# copter.net
KiCad netlist of a schematic drawn in EAGLE
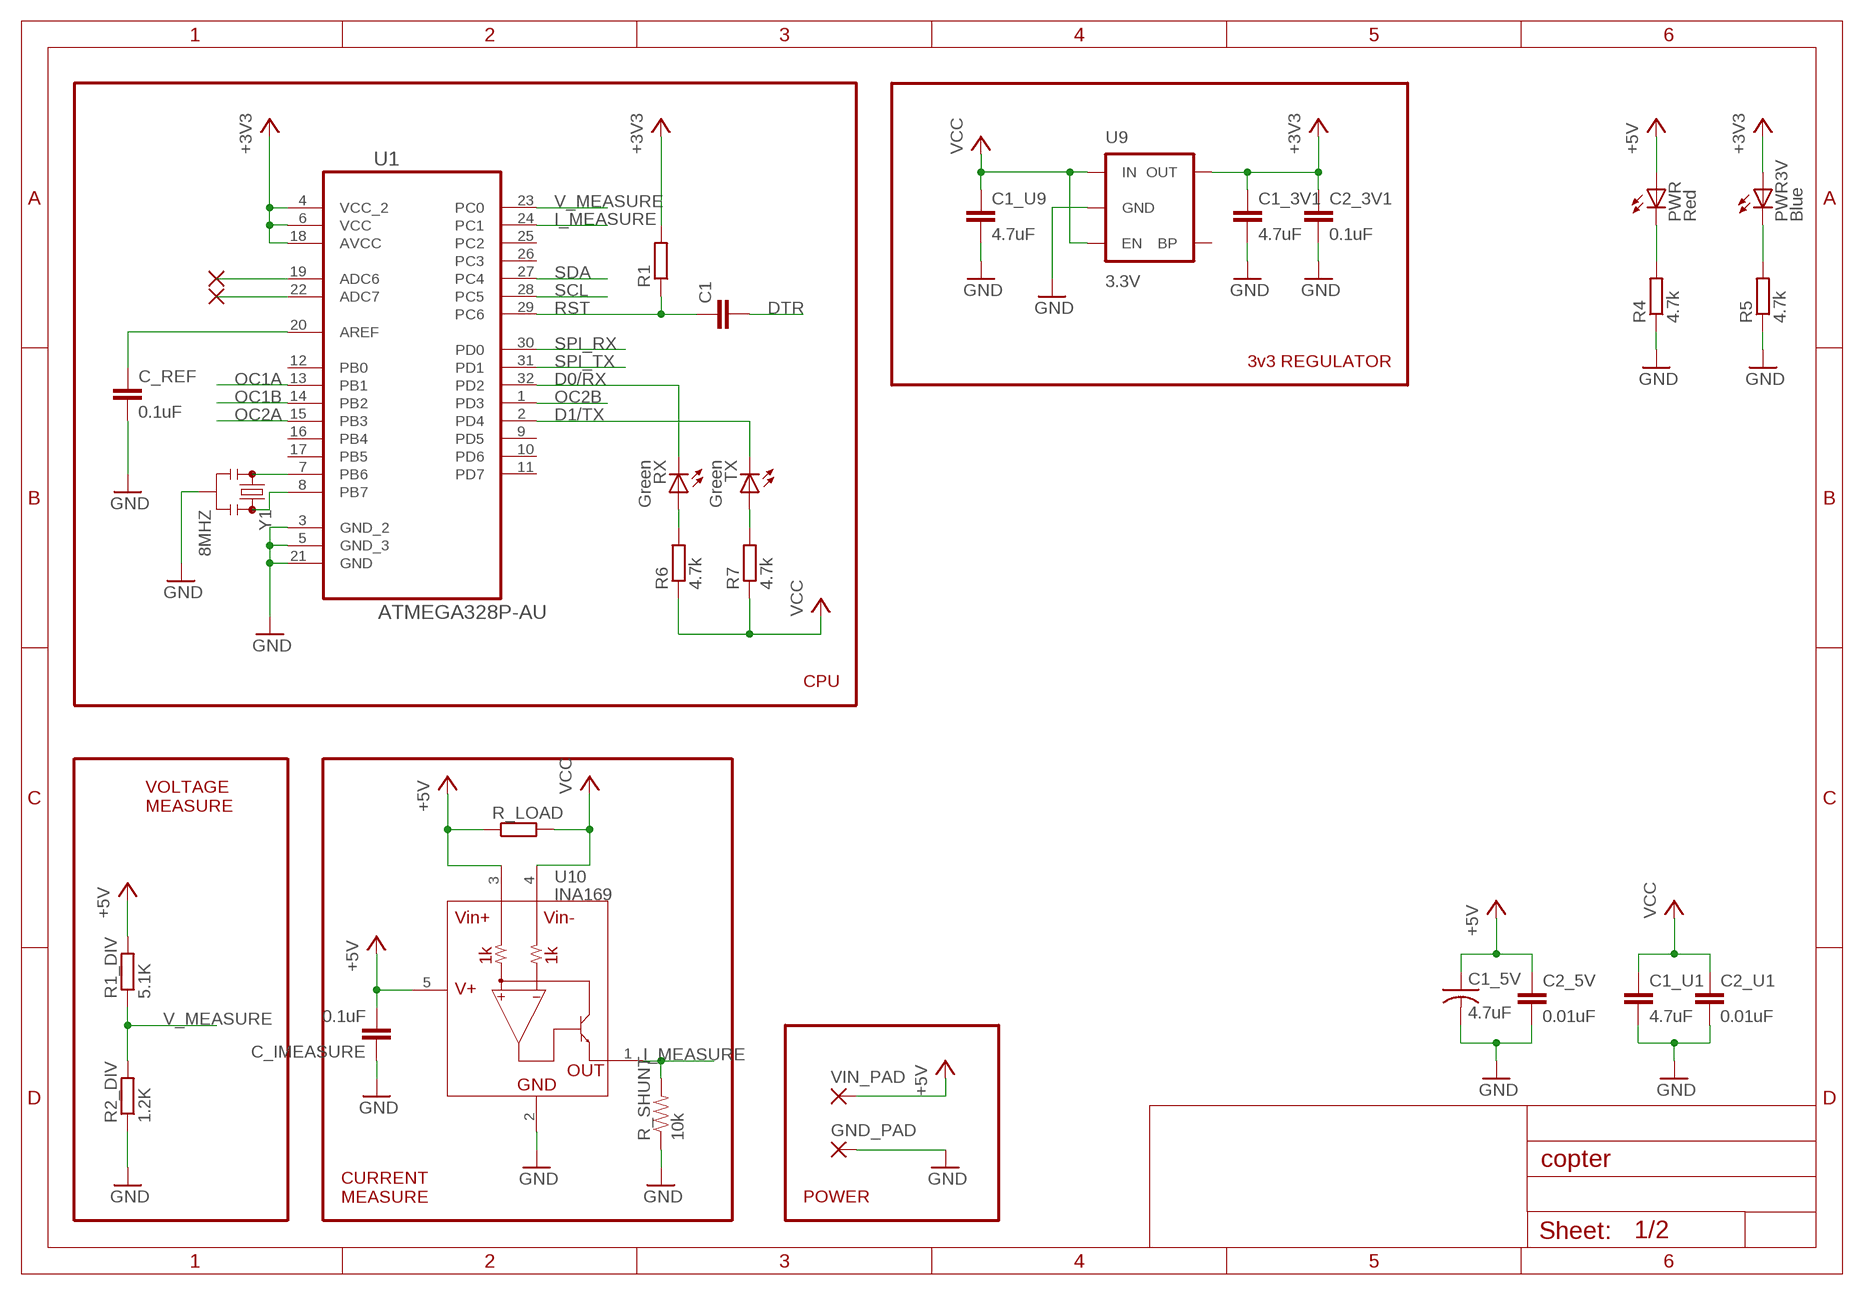
[diagram p0: schematic, sheet 1]
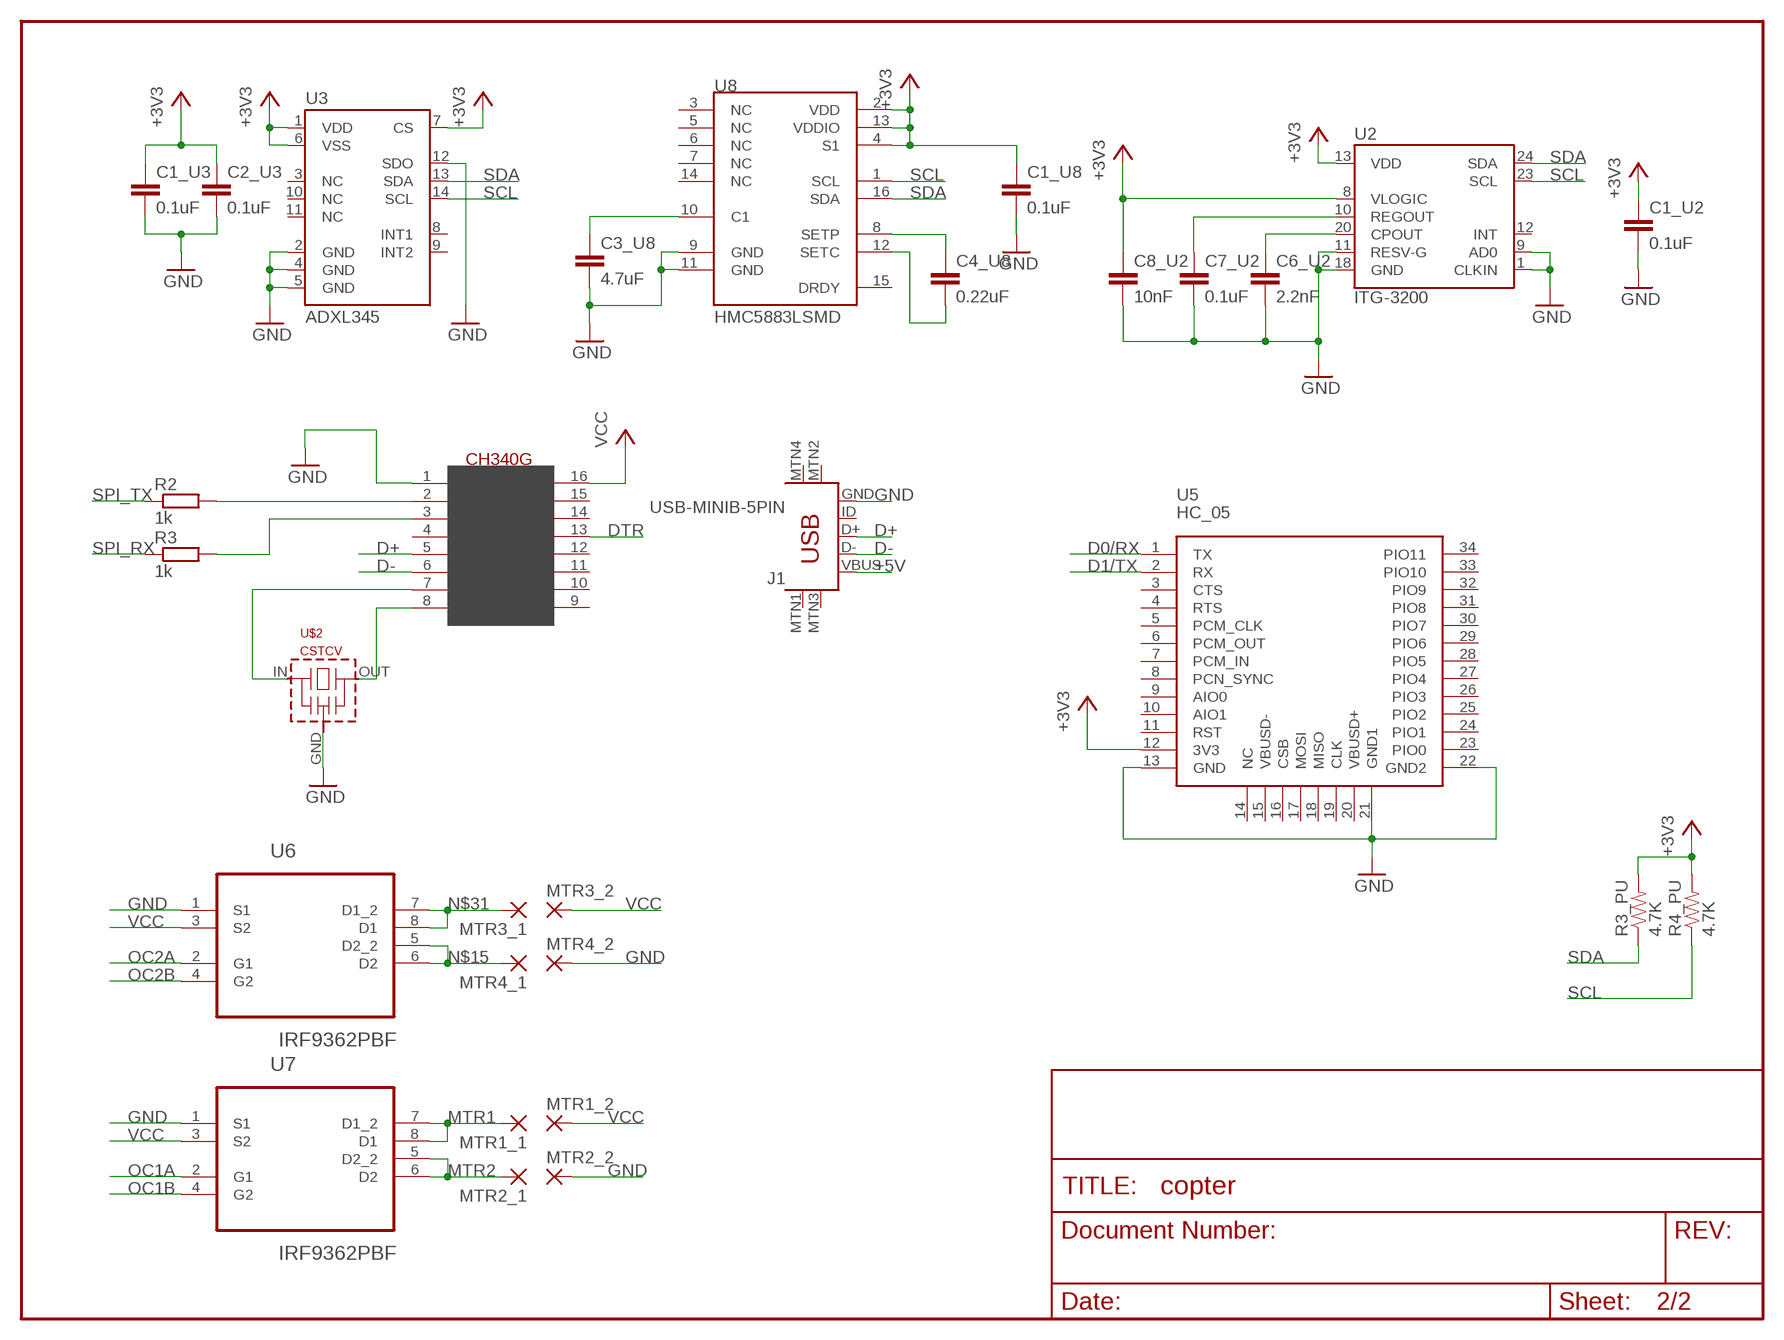
[diagram p1: schematic, sheet 2]

(export (version "E")
  (design (tool "Eeschema 10.0.6"))
  (components
    (comp (ref "C1_U2")
      (value "0.1uF")
      (footprint "eagle-import:0402-CAP")
      (libsource (lib "eagle-import") (part "CAP0402-CAP"))
    )
    (comp (ref "C1_U3")
      (value "0.1uF")
      (footprint "eagle-import:0402-CAP")
      (libsource (lib "eagle-import") (part "CAP0402-CAP"))
    )
    (comp (ref "C1_U8")
      (value "0.1uF")
      (footprint "eagle-import:0402-CAP")
      (libsource (lib "eagle-import") (part "CAP0402-CAP"))
    )
    (comp (ref "C2_U3")
      (value "0.1uF")
      (footprint "eagle-import:0402-CAP")
      (libsource (lib "eagle-import") (part "CAP0402-CAP"))
    )
    (comp (ref "C3_U8")
      (value "4.7uF")
      (footprint "eagle-import:0402-CAP")
      (libsource (lib "eagle-import") (part "CAP0402-CAP"))
    )
    (comp (ref "C4_U8")
      (value "0.22uF")
      (footprint "eagle-import:0402-CAP")
      (libsource (lib "eagle-import") (part "CAP0402-CAP"))
    )
    (comp (ref "C6_U2")
      (value "2.2nF")
      (footprint "eagle-import:0402-CAP")
      (libsource (lib "eagle-import") (part "CAP0402-CAP"))
    )
    (comp (ref "C7_U2")
      (value "0.1uF")
      (footprint "eagle-import:0402-CAP")
      (libsource (lib "eagle-import") (part "CAP0402-CAP"))
    )
    (comp (ref "C8_U2")
      (value "10nF")
      (footprint "eagle-import:0402-CAP")
      (libsource (lib "eagle-import") (part "CAP0402-CAP"))
    )
    (comp (ref "J1")
      (value "USB-MINIB-5PIN")
      (footprint "eagle-import:USB-MINIB")
      (libsource (lib "eagle-import") (part "USB-MINIB-5PIN"))
    )
    (comp (ref "MTR1_1")
      (value "1,6/0,8")
      (footprint "eagle-import:1,6_0,8")
      (libsource (lib "eagle-import") (part "1,6/0,8"))
    )
    (comp (ref "MTR1_2")
      (value "1,6/0,8")
      (footprint "eagle-import:1,6_0,8")
      (libsource (lib "eagle-import") (part "1,6/0,8"))
    )
    (comp (ref "MTR2_1")
      (value "1,6/0,8")
      (footprint "eagle-import:1,6_0,8")
      (libsource (lib "eagle-import") (part "1,6/0,8"))
    )
    (comp (ref "MTR2_2")
      (value "1,6/0,8")
      (footprint "eagle-import:1,6_0,8")
      (libsource (lib "eagle-import") (part "1,6/0,8"))
    )
    (comp (ref "MTR3_1")
      (value "1,6/0,8")
      (footprint "eagle-import:1,6_0,8")
      (libsource (lib "eagle-import") (part "1,6/0,8"))
    )
    (comp (ref "MTR3_2")
      (value "1,6/0,8")
      (footprint "eagle-import:1,6_0,8")
      (libsource (lib "eagle-import") (part "1,6/0,8"))
    )
    (comp (ref "MTR4_1")
      (value "1,6/0,8")
      (footprint "eagle-import:1,6_0,8")
      (libsource (lib "eagle-import") (part "1,6/0,8"))
    )
    (comp (ref "MTR4_2")
      (value "1,6/0,8")
      (footprint "eagle-import:1,6_0,8")
      (libsource (lib "eagle-import") (part "1,6/0,8"))
    )
    (comp (ref "R2")
      (value "1k")
      (footprint "eagle-import:R0402")
      (libsource (lib "eagle-import") (part "resistor_R-EU_R0402"))
    )
    (comp (ref "R3")
      (value "1k")
      (footprint "eagle-import:R0402")
      (libsource (lib "eagle-import") (part "resistor_R-EU_R0402"))
    )
    (comp (ref "R3_PU")
      (value "4.7K")
      (footprint "eagle-import:0402-RES")
      (libsource (lib "eagle-import") (part "RESISTOR0402-RES"))
    )
    (comp (ref "R4_PU")
      (value "4.7K")
      (footprint "eagle-import:0402-RES")
      (libsource (lib "eagle-import") (part "RESISTOR0402-RES"))
    )
    (comp (ref "U$1")
      (value "CH340G")
      (footprint "eagle-import:SOIC16")
      (libsource (lib "eagle-import") (part "CH340G"))
    )
    (comp (ref "U$2")
      (value "CSTCV")
      (footprint "eagle-import:CSTCV")
      (libsource (lib "eagle-import") (part "CSTCV"))
    )
    (comp (ref "U2")
      (value "ITG-3200")
      (footprint "eagle-import:QFN-24")
      (libsource (lib "eagle-import") (part "ITG-3200"))
    )
    (comp (ref "U3")
      (value "ADXL345")
      (footprint "eagle-import:LGA14")
      (libsource (lib "eagle-import") (part "ADXL345"))
    )
    (comp (ref "U5")
      (value "HC_05")
      (footprint "eagle-import:BLUETOOTH_SMD")
      (libsource (lib "eagle-import") (part "HC_05"))
    )
    (comp (ref "U6")
      (value "IRF9362PBF")
      (footprint "eagle-import:SOIC127P600X175-8N")
      (libsource (lib "eagle-import") (part "IRF9362PBF"))
    )
    (comp (ref "U7")
      (value "IRF9362PBF")
      (footprint "eagle-import:SOIC127P600X175-8N")
      (libsource (lib "eagle-import") (part "IRF9362PBF"))
    )
    (comp (ref "U8")
      (value "HMC5883LSMD")
      (footprint "eagle-import:16LPCC")
      (libsource (lib "eagle-import") (part "HMC5883LSMD"))
    )
    (comp (ref "C1")
      (value "C-EUC0402")
      (footprint "eagle-import:C0402")
      (libsource (lib "eagle-import") (part "C-EUC0402"))
    )
    (comp (ref "C1_3V1")
      (value "4.7uF")
      (footprint "eagle-import:0402-CAP")
      (libsource (lib "eagle-import") (part "CAP0402-CAP"))
    )
    (comp (ref "C1_5V")
      (value "4.7uF")
      (footprint "eagle-import:C1210K")
      (libsource (lib "eagle-import") (part "C-USC1210K"))
    )
    (comp (ref "C1_U1")
      (value "4.7uF")
      (footprint "eagle-import:C1206")
      (libsource (lib "eagle-import") (part "resistor_C-EUC1206"))
    )
    (comp (ref "C1_U9")
      (value "4.7uF")
      (footprint "eagle-import:0402-CAP")
      (libsource (lib "eagle-import") (part "CAP0402-CAP"))
    )
    (comp (ref "C2_3V1")
      (value "0.1uF")
      (footprint "eagle-import:0402-CAP")
      (libsource (lib "eagle-import") (part "CAP0402-CAP"))
    )
    (comp (ref "C2_5V")
      (value "0.01uF")
      (footprint "eagle-import:C0402")
      (libsource (lib "eagle-import") (part "resistor_C-EUC0402"))
    )
    (comp (ref "C2_U1")
      (value "0.01uF")
      (footprint "eagle-import:C0402")
      (libsource (lib "eagle-import") (part "resistor_C-EUC0402"))
    )
    (comp (ref "C_IMEASURE")
      (value "0.1uF")
      (footprint "eagle-import:0603-CAP")
      (libsource (lib "eagle-import") (part "SparkFun-Passives_CAP0603-CAP"))
    )
    (comp (ref "C_REF")
      (value "0.1uF")
      (footprint "eagle-import:C0402")
      (libsource (lib "eagle-import") (part "resistor_C-EUC0402"))
    )
    (comp (ref "GND_PAD")
      (value "1,6/0,8")
      (footprint "eagle-import:1,6_0,8")
      (libsource (lib "eagle-import") (part "1,6/0,8"))
    )
    (comp (ref "PWR")
      (value "Red")
      (footprint "eagle-import:LED-0603")
      (libsource (lib "eagle-import") (part "LED0603"))
    )
    (comp (ref "PWR3V")
      (value "Blue")
      (footprint "eagle-import:LED-0603")
      (libsource (lib "eagle-import") (part "LED0603"))
    )
    (comp (ref "R1")
      (value "R-EU_R0402")
      (footprint "eagle-import:R0402")
      (libsource (lib "eagle-import") (part "R-EU_R0402"))
    )
    (comp (ref "R1_DIV")
      (value "5.1K")
      (footprint "eagle-import:R0402")
      (libsource (lib "eagle-import") (part "resistor_R-EU_R0402"))
    )
    (comp (ref "R2_DIV")
      (value "1.2K")
      (footprint "eagle-import:R0402")
      (libsource (lib "eagle-import") (part "resistor_R-EU_R0402"))
    )
    (comp (ref "R4")
      (value "4.7k")
      (footprint "eagle-import:R0402")
      (libsource (lib "eagle-import") (part "R-EU_R0402"))
    )
    (comp (ref "R5")
      (value "4.7k")
      (footprint "eagle-import:R0402")
      (libsource (lib "eagle-import") (part "R-EU_R0402"))
    )
    (comp (ref "R6")
      (value "4.7k")
      (footprint "eagle-import:R0402")
      (libsource (lib "eagle-import") (part "R-EU_R0402"))
    )
    (comp (ref "R7")
      (value "4.7k")
      (footprint "eagle-import:R0402")
      (libsource (lib "eagle-import") (part "R-EU_R0402"))
    )
    (comp (ref "RX")
      (value "Green")
      (footprint "eagle-import:LED-0603")
      (libsource (lib "eagle-import") (part "LED0603"))
    )
    (comp (ref "R_LOAD")
      (value "R-EU_0309/10")
      (footprint "eagle-import:0309_10")
      (fields (field (name "SIZE") "1206") (field (name "TOL") "1%"))
      (libsource (lib "eagle-import") (part "resistor_R-EU_0309/10"))
    )
    (comp (ref "R_SHUNT")
      (value "10k")
      (footprint "eagle-import:0603-RES")
      (fields (field (name "TOL") "1%"))
      (libsource (lib "eagle-import") (part "RESISTOR0603"))
    )
    (comp (ref "TX")
      (value "Green")
      (footprint "eagle-import:LED-0603")
      (libsource (lib "eagle-import") (part "LED0603"))
    )
    (comp (ref "U1")
      (value "ATMEGA328P-AU")
      (footprint "eagle-import:QFP80P900X900X120-32N")
      (libsource (lib "eagle-import") (part "ATMEGA328P-AU"))
    )
    (comp (ref "U9")
      (value "3.3V")
      (footprint "eagle-import:SOT23-5")
      (libsource (lib "eagle-import") (part "V_REG_LDOSMD"))
    )
    (comp (ref "U10")
      (value "INA169")
      (footprint "eagle-import:SOT23-5")
      (libsource (lib "eagle-import") (part "INA169"))
    )
    (comp (ref "VIN_PAD")
      (value "1,6/0,8")
      (footprint "eagle-import:1,6_0,8")
      (libsource (lib "eagle-import") (part "1,6/0,8"))
    )
    (comp (ref "Y1")
      (value "8MHZ")
      (footprint "eagle-import:RESONATOR-SMD")
      (libsource (lib "eagle-import") (part "RESONATOR8MHZ"))
    )
  )
  (nets
    (net (code "1") (name "+3V3") (class "Default")
      (node (ref "C1_3V1") (pin "1") (pinfunction "1_1") (pintype "passive"))
      (node (ref "C1_U2") (pin "1") (pinfunction "1_1") (pintype "passive"))
      (node (ref "C1_U3") (pin "1") (pinfunction "1_1") (pintype "passive"))
      (node (ref "C1_U8") (pin "1") (pinfunction "1_1") (pintype "passive"))
      (node (ref "C2_3V1") (pin "1") (pinfunction "1_1") (pintype "passive"))
      (node (ref "C2_U3") (pin "1") (pinfunction "1_1") (pintype "passive"))
      (node (ref "C8_U2") (pin "1") (pinfunction "1_1") (pintype "passive"))
      (node (ref "PWR3V") (pin "A") (pinfunction "A_A") (pintype "passive"))
      (node (ref "R1") (pin "2") (pinfunction "2_2") (pintype "passive"))
      (node (ref "R3_PU") (pin "2") (pinfunction "2_2") (pintype "passive"))
      (node (ref "R4_PU") (pin "2") (pinfunction "2_2") (pintype "passive"))
      (node (ref "U1") (pin "18") (pinfunction "AVCC_18") (pintype "power_in"))
      (node (ref "U1") (pin "4") (pinfunction "VCC_2_4") (pintype "power_in"))
      (node (ref "U1") (pin "6") (pinfunction "VCC_6") (pintype "power_in"))
      (node (ref "U2") (pin "13") (pinfunction "VDD_13") (pintype "bidirectional"))
      (node (ref "U2") (pin "8") (pinfunction "VLOGIC_8") (pintype "bidirectional"))
      (node (ref "U3") (pin "1") (pinfunction "VDD_1") (pintype "bidirectional"))
      (node (ref "U3") (pin "6") (pinfunction "VSS_6") (pintype "bidirectional"))
      (node (ref "U3") (pin "7") (pinfunction "CS_7") (pintype "bidirectional"))
      (node (ref "U5") (pin "12") (pinfunction "3V3_12") (pintype "bidirectional"))
      (node (ref "U8") (pin "13") (pinfunction "VDDIO_13") (pintype "bidirectional"))
      (node (ref "U8") (pin "2") (pinfunction "VDD_2") (pintype "bidirectional"))
      (node (ref "U8") (pin "4") (pinfunction "S1_4") (pintype "bidirectional"))
      (node (ref "U9") (pin "5") (pinfunction "OUT_5") (pintype "passive"))
    )
    (net (code "2") (name "+5V") (class "Default")
      (node (ref "C1_5V") (pin "1") (pinfunction "1_1") (pintype "passive"))
      (node (ref "C2_5V") (pin "1") (pinfunction "1_1") (pintype "passive"))
      (node (ref "C_IMEASURE") (pin "2") (pinfunction "2_2") (pintype "passive"))
      (node (ref "J1") (pin "VBUS") (pinfunction "VBUS_VBUS") (pintype "bidirectional"))
      (node (ref "PWR") (pin "A") (pinfunction "A_A") (pintype "passive"))
      (node (ref "R1_DIV") (pin "2") (pinfunction "2_2") (pintype "passive"))
      (node (ref "R_LOAD") (pin "1") (pinfunction "1_1") (pintype "passive"))
      (node (ref "U10") (pin "3") (pinfunction "VIN+_3") (pintype "bidirectional"))
      (node (ref "U10") (pin "5") (pinfunction "V+_5") (pintype "bidirectional"))
      (node (ref "VIN_PAD") (pin "1") (pinfunction "P_1") (pintype "passive"))
    )
    (net (code "3") (name "D+") (class "Default")
      (node (ref "J1") (pin "D+") (pinfunction "D+_D+") (pintype "bidirectional"))
      (node (ref "U$1") (pin "5") (pinfunction "D+_5") (pintype "bidirectional"))
    )
    (net (code "4") (name "D-") (class "Default")
      (node (ref "J1") (pin "D-") (pinfunction "D-_D-") (pintype "bidirectional"))
      (node (ref "U$1") (pin "6") (pinfunction "D-_6") (pintype "bidirectional"))
    )
    (net (code "5") (name "D0{slash}RX") (class "Default")
      (node (ref "RX") (pin "C") (pinfunction "C_C") (pintype "passive"))
      (node (ref "U1") (pin "32") (pinfunction "PD2_32") (pintype "bidirectional"))
      (node (ref "U5") (pin "1") (pinfunction "TX_1") (pintype "bidirectional"))
    )
    (net (code "6") (name "D1{slash}TX") (class "Default")
      (node (ref "TX") (pin "C") (pinfunction "C_C") (pintype "passive"))
      (node (ref "U1") (pin "2") (pinfunction "PD4_2") (pintype "bidirectional"))
      (node (ref "U5") (pin "2") (pinfunction "RX_2") (pintype "bidirectional"))
    )
    (net (code "7") (name "DTR") (class "Default")
      (node (ref "C1") (pin "2") (pinfunction "2_2") (pintype "passive"))
      (node (ref "U$1") (pin "13") (pinfunction "DTR_13") (pintype "bidirectional"))
    )
    (net (code "8") (name "GND") (class "Default")
      (node (ref "C1_3V1") (pin "2") (pinfunction "2_2") (pintype "passive"))
      (node (ref "C1_5V") (pin "2") (pinfunction "2_2") (pintype "passive"))
      (node (ref "C1_U1") (pin "2") (pinfunction "2_2") (pintype "passive"))
      (node (ref "C1_U2") (pin "2") (pinfunction "2_2") (pintype "passive"))
      (node (ref "C1_U3") (pin "2") (pinfunction "2_2") (pintype "passive"))
      (node (ref "C1_U8") (pin "2") (pinfunction "2_2") (pintype "passive"))
      (node (ref "C1_U9") (pin "2") (pinfunction "2_2") (pintype "passive"))
      (node (ref "C2_3V1") (pin "2") (pinfunction "2_2") (pintype "passive"))
      (node (ref "C2_5V") (pin "2") (pinfunction "2_2") (pintype "passive"))
      (node (ref "C2_U1") (pin "2") (pinfunction "2_2") (pintype "passive"))
      (node (ref "C2_U3") (pin "2") (pinfunction "2_2") (pintype "passive"))
      (node (ref "C3_U8") (pin "2") (pinfunction "2_2") (pintype "passive"))
      (node (ref "C6_U2") (pin "2") (pinfunction "2_2") (pintype "passive"))
      (node (ref "C7_U2") (pin "2") (pinfunction "2_2") (pintype "passive"))
      (node (ref "C8_U2") (pin "2") (pinfunction "2_2") (pintype "passive"))
      (node (ref "C_IMEASURE") (pin "1") (pinfunction "1_1") (pintype "passive"))
      (node (ref "C_REF") (pin "2") (pinfunction "2_2") (pintype "passive"))
      (node (ref "GND_PAD") (pin "1") (pinfunction "P_1") (pintype "passive"))
      (node (ref "J1") (pin "GND") (pinfunction "GND_GND") (pintype "bidirectional"))
      (node (ref "MTR2_2") (pin "1") (pinfunction "P_1") (pintype "passive"))
      (node (ref "MTR4_2") (pin "1") (pinfunction "P_1") (pintype "passive"))
      (node (ref "R2_DIV") (pin "1") (pinfunction "1_1") (pintype "passive"))
      (node (ref "R4") (pin "1") (pinfunction "1_1") (pintype "passive"))
      (node (ref "R5") (pin "1") (pinfunction "1_1") (pintype "passive"))
      (node (ref "R_SHUNT") (pin "1") (pinfunction "1_1") (pintype "passive"))
      (node (ref "U$1") (pin "1") (pinfunction "GND_1") (pintype "bidirectional"))
      (node (ref "U$2") (pin "GND") (pinfunction "GND_GND") (pintype "power_in"))
      (node (ref "U1") (pin "21") (pinfunction "GND_21") (pintype "passive"))
      (node (ref "U1") (pin "3") (pinfunction "GND_2_3") (pintype "passive"))
      (node (ref "U1") (pin "5") (pinfunction "GND_3_5") (pintype "passive"))
      (node (ref "U10") (pin "2") (pinfunction "GND_2") (pintype "bidirectional"))
      (node (ref "U2") (pin "1") (pinfunction "CLKIN_1") (pintype "bidirectional"))
      (node (ref "U2") (pin "11") (pinfunction "RESV-G_11") (pintype "bidirectional"))
      (node (ref "U2") (pin "18") (pinfunction "GND_18") (pintype "bidirectional"))
      (node (ref "U2") (pin "9") (pinfunction "AD0_9") (pintype "bidirectional"))
      (node (ref "U3") (pin "12") (pinfunction "SDO_12") (pintype "bidirectional"))
      (node (ref "U3") (pin "2") (pinfunction "GND_2") (pintype "bidirectional"))
      (node (ref "U3") (pin "4") (pinfunction "GND_4") (pintype "bidirectional"))
      (node (ref "U3") (pin "5") (pinfunction "GND_5") (pintype "bidirectional"))
      (node (ref "U5") (pin "13") (pinfunction "GND_13") (pintype "bidirectional"))
      (node (ref "U5") (pin "21") (pinfunction "GND1_21") (pintype "bidirectional"))
      (node (ref "U5") (pin "22") (pinfunction "GND2_22") (pintype "bidirectional"))
      (node (ref "U6") (pin "1") (pinfunction "S1_1") (pintype "passive"))
      (node (ref "U7") (pin "1") (pinfunction "S1_1") (pintype "passive"))
      (node (ref "U8") (pin "11") (pinfunction "GND_11") (pintype "bidirectional"))
      (node (ref "U8") (pin "9") (pinfunction "GND_9") (pintype "bidirectional"))
      (node (ref "U9") (pin "2") (pinfunction "GND_2") (pintype "input"))
      (node (ref "Y1") (pin "2") (pinfunction "2_2") (pintype "passive"))
    )
    (net (code "9") (name "I_MEASURE") (class "Default")
      (node (ref "R_SHUNT") (pin "2") (pinfunction "2_2") (pintype "passive"))
      (node (ref "U1") (pin "24") (pinfunction "PC1_24") (pintype "bidirectional"))
      (node (ref "U10") (pin "1") (pinfunction "OUT_1") (pintype "bidirectional"))
    )
    (net (code "10") (name "MTR1") (class "Default")
      (node (ref "MTR1_1") (pin "1") (pinfunction "P_1") (pintype "passive"))
      (node (ref "U7") (pin "7") (pinfunction "D1_2_7") (pintype "passive"))
      (node (ref "U7") (pin "8") (pinfunction "D1_8") (pintype "passive"))
    )
    (net (code "11") (name "MTR2") (class "Default")
      (node (ref "MTR2_1") (pin "1") (pinfunction "P_1") (pintype "passive"))
      (node (ref "U7") (pin "5") (pinfunction "D2_2_5") (pintype "passive"))
      (node (ref "U7") (pin "6") (pinfunction "D2_6") (pintype "passive"))
    )
    (net (code "12") (name "N$15") (class "Default")
      (node (ref "MTR4_1") (pin "1") (pinfunction "P_1") (pintype "passive"))
      (node (ref "U6") (pin "5") (pinfunction "D2_2_5") (pintype "passive"))
      (node (ref "U6") (pin "6") (pinfunction "D2_6") (pintype "passive"))
    )
    (net (code "13") (name "N$31") (class "Default")
      (node (ref "MTR3_1") (pin "1") (pinfunction "P_1") (pintype "passive"))
      (node (ref "U6") (pin "7") (pinfunction "D1_2_7") (pintype "passive"))
      (node (ref "U6") (pin "8") (pinfunction "D1_8") (pintype "passive"))
    )
    (net (code "14") (name "Net-(PWR-PadC)") (class "Default")
      (node (ref "PWR") (pin "C") (pinfunction "C_C") (pintype "passive"))
      (node (ref "R4") (pin "2") (pinfunction "2_2") (pintype "passive"))
    )
    (net (code "15") (name "Net-(PWR3V-PadC)") (class "Default")
      (node (ref "PWR3V") (pin "C") (pinfunction "C_C") (pintype "passive"))
      (node (ref "R5") (pin "2") (pinfunction "2_2") (pintype "passive"))
    )
    (net (code "16") (name "Net-(R6-Pad2)") (class "Default")
      (node (ref "R6") (pin "2") (pinfunction "2_2") (pintype "passive"))
      (node (ref "RX") (pin "A") (pinfunction "A_A") (pintype "passive"))
    )
    (net (code "17") (name "Net-(R7-Pad2)") (class "Default")
      (node (ref "R7") (pin "2") (pinfunction "2_2") (pintype "passive"))
      (node (ref "TX") (pin "A") (pinfunction "A_A") (pintype "passive"))
    )
    (net (code "18") (name "Net-(U$1-RX)") (class "Default")
      (node (ref "R3") (pin "2") (pinfunction "2_2") (pintype "passive"))
      (node (ref "U$1") (pin "3") (pinfunction "RX_3") (pintype "bidirectional"))
    )
    (net (code "19") (name "Net-(U$1-TX)") (class "Default")
      (node (ref "R2") (pin "2") (pinfunction "2_2") (pintype "passive"))
      (node (ref "U$1") (pin "2") (pinfunction "TX_2") (pintype "bidirectional"))
    )
    (net (code "20") (name "Net-(U$1-XI)") (class "Default")
      (node (ref "U$1") (pin "7") (pinfunction "XI_7") (pintype "bidirectional"))
      (node (ref "U$2") (pin "IN") (pinfunction "IN_IN") (pintype "input"))
    )
    (net (code "21") (name "Net-(U$1-XO)") (class "Default")
      (node (ref "U$1") (pin "8") (pinfunction "XO_8") (pintype "bidirectional"))
      (node (ref "U$2") (pin "OUT") (pinfunction "OUT_OUT") (pintype "output"))
    )
    (net (code "22") (name "Net-(U1-AREF)") (class "Default")
      (node (ref "C_REF") (pin "1") (pinfunction "1_1") (pintype "passive"))
      (node (ref "U1") (pin "20") (pinfunction "AREF_20") (pintype "input"))
    )
    (net (code "23") (name "Net-(U1-PB6)") (class "Default")
      (node (ref "U1") (pin "7") (pinfunction "PB6_7") (pintype "bidirectional"))
      (node (ref "Y1") (pin "1") (pinfunction "1_1") (pintype "passive"))
    )
    (net (code "24") (name "Net-(U1-PB7)") (class "Default")
      (node (ref "U1") (pin "8") (pinfunction "PB7_8") (pintype "bidirectional"))
      (node (ref "Y1") (pin "3") (pinfunction "3_3") (pintype "passive"))
    )
    (net (code "25") (name "Net-(U2-CPOUT)") (class "Default")
      (node (ref "C6_U2") (pin "1") (pinfunction "1_1") (pintype "passive"))
      (node (ref "U2") (pin "20") (pinfunction "CPOUT_20") (pintype "bidirectional"))
    )
    (net (code "26") (name "Net-(U2-REGOUT)") (class "Default")
      (node (ref "C7_U2") (pin "1") (pinfunction "1_1") (pintype "passive"))
      (node (ref "U2") (pin "10") (pinfunction "REGOUT_10") (pintype "bidirectional"))
    )
    (net (code "27") (name "Net-(U8-C1)") (class "Default")
      (node (ref "C3_U8") (pin "1") (pinfunction "1_1") (pintype "passive"))
      (node (ref "U8") (pin "10") (pinfunction "C1_10") (pintype "bidirectional"))
    )
    (net (code "28") (name "Net-(U8-SETC)") (class "Default")
      (node (ref "C4_U8") (pin "2") (pinfunction "2_2") (pintype "passive"))
      (node (ref "U8") (pin "12") (pinfunction "SETC_12") (pintype "bidirectional"))
    )
    (net (code "29") (name "Net-(U8-SETP)") (class "Default")
      (node (ref "C4_U8") (pin "1") (pinfunction "1_1") (pintype "passive"))
      (node (ref "U8") (pin "8") (pinfunction "SETP_8") (pintype "bidirectional"))
    )
    (net (code "30") (name "OC1A") (class "Default")
      (node (ref "U1") (pin "13") (pinfunction "PB1_13") (pintype "bidirectional"))
      (node (ref "U7") (pin "2") (pinfunction "G1_2") (pintype "passive"))
    )
    (net (code "31") (name "OC1B") (class "Default")
      (node (ref "U1") (pin "14") (pinfunction "PB2_14") (pintype "bidirectional"))
      (node (ref "U7") (pin "4") (pinfunction "G2_4") (pintype "passive"))
    )
    (net (code "32") (name "OC2A") (class "Default")
      (node (ref "U1") (pin "15") (pinfunction "PB3_15") (pintype "bidirectional"))
      (node (ref "U6") (pin "2") (pinfunction "G1_2") (pintype "passive"))
    )
    (net (code "33") (name "OC2B") (class "Default")
      (node (ref "U1") (pin "1") (pinfunction "PD3_1") (pintype "bidirectional"))
      (node (ref "U6") (pin "4") (pinfunction "G2_4") (pintype "passive"))
    )
    (net (code "34") (name "RST") (class "Default")
      (node (ref "C1") (pin "1") (pinfunction "1_1") (pintype "passive"))
      (node (ref "R1") (pin "1") (pinfunction "1_1") (pintype "passive"))
      (node (ref "U1") (pin "29") (pinfunction "PC6_29") (pintype "bidirectional"))
    )
    (net (code "35") (name "SCL") (class "Default")
      (node (ref "R4_PU") (pin "1") (pinfunction "1_1") (pintype "passive"))
      (node (ref "U1") (pin "28") (pinfunction "PC5_28") (pintype "bidirectional"))
      (node (ref "U2") (pin "23") (pinfunction "SCL_23") (pintype "bidirectional"))
      (node (ref "U3") (pin "14") (pinfunction "SCL_14") (pintype "bidirectional"))
      (node (ref "U8") (pin "1") (pinfunction "SCL_1") (pintype "bidirectional"))
    )
    (net (code "36") (name "SDA") (class "Default")
      (node (ref "R3_PU") (pin "1") (pinfunction "1_1") (pintype "passive"))
      (node (ref "U1") (pin "27") (pinfunction "PC4_27") (pintype "bidirectional"))
      (node (ref "U2") (pin "24") (pinfunction "SDA_24") (pintype "bidirectional"))
      (node (ref "U3") (pin "13") (pinfunction "SDA_13") (pintype "bidirectional"))
      (node (ref "U8") (pin "16") (pinfunction "SDA_16") (pintype "bidirectional"))
    )
    (net (code "37") (name "SPI_RX") (class "Default")
      (node (ref "R3") (pin "1") (pinfunction "1_1") (pintype "passive"))
      (node (ref "U1") (pin "30") (pinfunction "PD0_30") (pintype "bidirectional"))
    )
    (net (code "38") (name "SPI_TX") (class "Default")
      (node (ref "R2") (pin "1") (pinfunction "1_1") (pintype "passive"))
      (node (ref "U1") (pin "31") (pinfunction "PD1_31") (pintype "bidirectional"))
    )
    (net (code "39") (name "VCC") (class "Default")
      (node (ref "C1_U1") (pin "1") (pinfunction "1_1") (pintype "passive"))
      (node (ref "C1_U9") (pin "1") (pinfunction "1_1") (pintype "passive"))
      (node (ref "C2_U1") (pin "1") (pinfunction "1_1") (pintype "passive"))
      (node (ref "MTR1_2") (pin "1") (pinfunction "P_1") (pintype "passive"))
      (node (ref "MTR3_2") (pin "1") (pinfunction "P_1") (pintype "passive"))
      (node (ref "R6") (pin "1") (pinfunction "1_1") (pintype "passive"))
      (node (ref "R7") (pin "1") (pinfunction "1_1") (pintype "passive"))
      (node (ref "R_LOAD") (pin "2") (pinfunction "2_2") (pintype "passive"))
      (node (ref "U$1") (pin "16") (pinfunction "VCC_16") (pintype "bidirectional"))
      (node (ref "U10") (pin "4") (pinfunction "VIN-_4") (pintype "bidirectional"))
      (node (ref "U6") (pin "3") (pinfunction "S2_3") (pintype "passive"))
      (node (ref "U7") (pin "3") (pinfunction "S2_3") (pintype "passive"))
      (node (ref "U9") (pin "1") (pinfunction "IN_1") (pintype "input"))
      (node (ref "U9") (pin "3") (pinfunction "EN_3") (pintype "input"))
    )
    (net (code "40") (name "V_MEASURE") (class "Default")
      (node (ref "R1_DIV") (pin "1") (pinfunction "1_1") (pintype "passive"))
      (node (ref "R2_DIV") (pin "2") (pinfunction "2_2") (pintype "passive"))
      (node (ref "U1") (pin "23") (pinfunction "PC0_23") (pintype "bidirectional"))
    )
    (net (code "41") (name "unconnected-(J1-MTN1-PadMTN3)") (class "Default")
      (node (ref "J1") (pin "MTN3") (pinfunction "MTN1_MTN3") (pintype "bidirectional"))
    )
    (net (code "42") (name "unconnected-(J1-MTN2-PadMTN1)") (class "Default")
      (node (ref "J1") (pin "MTN1") (pinfunction "MTN2_MTN1") (pintype "bidirectional"))
    )
    (net (code "43") (name "unconnected-(J1-MTN3-PadMTN2)") (class "Default")
      (node (ref "J1") (pin "MTN2") (pinfunction "MTN3_MTN2") (pintype "bidirectional"))
    )
    (net (code "44") (name "unconnected-(J1-PadID)") (class "Default")
      (node (ref "J1") (pin "ID") (pinfunction "ID_ID") (pintype "bidirectional"))
    )
    (net (code "45") (name "unconnected-(J1-PadMTN4)") (class "Default")
      (node (ref "J1") (pin "MTN4") (pinfunction "MTN4_MTN4") (pintype "bidirectional"))
    )
    (net (code "46") (name "unconnected-(U$1-CTS-Pad9)") (class "Default")
      (node (ref "U$1") (pin "9") (pinfunction "CTS_9") (pintype "bidirectional"))
    )
    (net (code "47") (name "unconnected-(U$1-DCD-Pad12)") (class "Default")
      (node (ref "U$1") (pin "12") (pinfunction "DCD_12") (pintype "bidirectional"))
    )
    (net (code "48") (name "unconnected-(U$1-DSR-Pad10)") (class "Default")
      (node (ref "U$1") (pin "10") (pinfunction "DSR_10") (pintype "bidirectional"))
    )
    (net (code "49") (name "unconnected-(U$1-RI-Pad11)") (class "Default")
      (node (ref "U$1") (pin "11") (pinfunction "RI_11") (pintype "bidirectional"))
    )
    (net (code "50") (name "unconnected-(U$1-RS232-Pad15)") (class "Default")
      (node (ref "U$1") (pin "15") (pinfunction "RS232_15") (pintype "bidirectional"))
    )
    (net (code "51") (name "unconnected-(U$1-RTS-Pad14)") (class "Default")
      (node (ref "U$1") (pin "14") (pinfunction "RTS_14") (pintype "bidirectional"))
    )
    (net (code "52") (name "unconnected-(U$1-V3-Pad4)") (class "Default")
      (node (ref "U$1") (pin "4") (pinfunction "V3_4") (pintype "bidirectional"))
    )
    (net (code "53") (name "unconnected-(U1-ADC6-Pad19)") (class "Default")
      (node (ref "U1") (pin "19") (pinfunction "ADC6_19") (pintype "input"))
    )
    (net (code "54") (name "unconnected-(U1-ADC7-Pad22)") (class "Default")
      (node (ref "U1") (pin "22") (pinfunction "ADC7_22") (pintype "input"))
    )
    (net (code "55") (name "unconnected-(U1-PB0-Pad12)") (class "Default")
      (node (ref "U1") (pin "12") (pinfunction "PB0_12") (pintype "bidirectional"))
    )
    (net (code "56") (name "unconnected-(U1-PB4-Pad16)") (class "Default")
      (node (ref "U1") (pin "16") (pinfunction "PB4_16") (pintype "bidirectional"))
    )
    (net (code "57") (name "unconnected-(U1-PB5-Pad17)") (class "Default")
      (node (ref "U1") (pin "17") (pinfunction "PB5_17") (pintype "bidirectional"))
    )
    (net (code "58") (name "unconnected-(U1-PC2-Pad25)") (class "Default")
      (node (ref "U1") (pin "25") (pinfunction "PC2_25") (pintype "bidirectional"))
    )
    (net (code "59") (name "unconnected-(U1-PC3-Pad26)") (class "Default")
      (node (ref "U1") (pin "26") (pinfunction "PC3_26") (pintype "bidirectional"))
    )
    (net (code "60") (name "unconnected-(U1-PD5-Pad9)") (class "Default")
      (node (ref "U1") (pin "9") (pinfunction "PD5_9") (pintype "bidirectional"))
    )
    (net (code "61") (name "unconnected-(U1-PD6-Pad10)") (class "Default")
      (node (ref "U1") (pin "10") (pinfunction "PD6_10") (pintype "bidirectional"))
    )
    (net (code "62") (name "unconnected-(U1-PD7-Pad11)") (class "Default")
      (node (ref "U1") (pin "11") (pinfunction "PD7_11") (pintype "bidirectional"))
    )
    (net (code "63") (name "unconnected-(U2-INT-Pad12)") (class "Default")
      (node (ref "U2") (pin "12") (pinfunction "INT_12") (pintype "bidirectional"))
    )
    (net (code "64") (name "unconnected-(U3-INT1-Pad8)") (class "Default")
      (node (ref "U3") (pin "8") (pinfunction "INT1_8") (pintype "bidirectional"))
    )
    (net (code "65") (name "unconnected-(U3-INT2-Pad9)") (class "Default")
      (node (ref "U3") (pin "9") (pinfunction "INT2_9") (pintype "bidirectional"))
    )
    (net (code "66") (name "unconnected-(U3-NC-Pad3)") (class "Default")
      (node (ref "U3") (pin "3") (pinfunction "NC_3") (pintype "bidirectional"))
    )
    (net (code "67") (name "unconnected-(U3-NC-Pad10)") (class "Default")
      (node (ref "U3") (pin "10") (pinfunction "NC_10") (pintype "bidirectional"))
    )
    (net (code "68") (name "unconnected-(U3-NC-Pad11)") (class "Default")
      (node (ref "U3") (pin "11") (pinfunction "NC_11") (pintype "bidirectional"))
    )
    (net (code "69") (name "unconnected-(U5-AIO0-Pad9)") (class "Default")
      (node (ref "U5") (pin "9") (pinfunction "AIO0_9") (pintype "bidirectional"))
    )
    (net (code "70") (name "unconnected-(U5-AIO1-Pad10)") (class "Default")
      (node (ref "U5") (pin "10") (pinfunction "AIO1_10") (pintype "bidirectional"))
    )
    (net (code "71") (name "unconnected-(U5-CLK-Pad19)") (class "Default")
      (node (ref "U5") (pin "19") (pinfunction "CLK_19") (pintype "bidirectional"))
    )
    (net (code "72") (name "unconnected-(U5-CSB-Pad16)") (class "Default")
      (node (ref "U5") (pin "16") (pinfunction "CSB_16") (pintype "bidirectional"))
    )
    (net (code "73") (name "unconnected-(U5-CTS-Pad3)") (class "Default")
      (node (ref "U5") (pin "3") (pinfunction "CTS_3") (pintype "bidirectional"))
    )
    (net (code "74") (name "unconnected-(U5-MISO-Pad18)") (class "Default")
      (node (ref "U5") (pin "18") (pinfunction "MISO_18") (pintype "bidirectional"))
    )
    (net (code "75") (name "unconnected-(U5-MOSI-Pad17)") (class "Default")
      (node (ref "U5") (pin "17") (pinfunction "MOSI_17") (pintype "bidirectional"))
    )
    (net (code "76") (name "unconnected-(U5-NC-Pad14)") (class "Default")
      (node (ref "U5") (pin "14") (pinfunction "NC_14") (pintype "bidirectional"))
    )
    (net (code "77") (name "unconnected-(U5-PCM_CLK-Pad5)") (class "Default")
      (node (ref "U5") (pin "5") (pinfunction "PCM_CLK_5") (pintype "bidirectional"))
    )
    (net (code "78") (name "unconnected-(U5-PCM_IN-Pad7)") (class "Default")
      (node (ref "U5") (pin "7") (pinfunction "PCM_IN_7") (pintype "bidirectional"))
    )
    (net (code "79") (name "unconnected-(U5-PCM_OUT-Pad6)") (class "Default")
      (node (ref "U5") (pin "6") (pinfunction "PCM_OUT_6") (pintype "bidirectional"))
    )
    (net (code "80") (name "unconnected-(U5-PCN_SYNC-Pad8)") (class "Default")
      (node (ref "U5") (pin "8") (pinfunction "PCN_SYNC_8") (pintype "bidirectional"))
    )
    (net (code "81") (name "unconnected-(U5-PIO0-Pad23)") (class "Default")
      (node (ref "U5") (pin "23") (pinfunction "PIO0_23") (pintype "bidirectional"))
    )
    (net (code "82") (name "unconnected-(U5-PIO1-Pad24)") (class "Default")
      (node (ref "U5") (pin "24") (pinfunction "PIO1_24") (pintype "bidirectional"))
    )
    (net (code "83") (name "unconnected-(U5-PIO2-Pad25)") (class "Default")
      (node (ref "U5") (pin "25") (pinfunction "PIO2_25") (pintype "bidirectional"))
    )
    (net (code "84") (name "unconnected-(U5-PIO3-Pad26)") (class "Default")
      (node (ref "U5") (pin "26") (pinfunction "PIO3_26") (pintype "bidirectional"))
    )
    (net (code "85") (name "unconnected-(U5-PIO4-Pad27)") (class "Default")
      (node (ref "U5") (pin "27") (pinfunction "PIO4_27") (pintype "bidirectional"))
    )
    (net (code "86") (name "unconnected-(U5-PIO5-Pad28)") (class "Default")
      (node (ref "U5") (pin "28") (pinfunction "PIO5_28") (pintype "bidirectional"))
    )
    (net (code "87") (name "unconnected-(U5-PIO6-Pad29)") (class "Default")
      (node (ref "U5") (pin "29") (pinfunction "PIO6_29") (pintype "bidirectional"))
    )
    (net (code "88") (name "unconnected-(U5-PIO7-Pad30)") (class "Default")
      (node (ref "U5") (pin "30") (pinfunction "PIO7_30") (pintype "bidirectional"))
    )
    (net (code "89") (name "unconnected-(U5-PIO8-Pad31)") (class "Default")
      (node (ref "U5") (pin "31") (pinfunction "PIO8_31") (pintype "bidirectional"))
    )
    (net (code "90") (name "unconnected-(U5-PIO9-Pad32)") (class "Default")
      (node (ref "U5") (pin "32") (pinfunction "PIO9_32") (pintype "bidirectional"))
    )
    (net (code "91") (name "unconnected-(U5-PIO10-Pad33)") (class "Default")
      (node (ref "U5") (pin "33") (pinfunction "PIO10_33") (pintype "bidirectional"))
    )
    (net (code "92") (name "unconnected-(U5-PIO11-Pad34)") (class "Default")
      (node (ref "U5") (pin "34") (pinfunction "PIO11_34") (pintype "bidirectional"))
    )
    (net (code "93") (name "unconnected-(U5-RST-Pad11)") (class "Default")
      (node (ref "U5") (pin "11") (pinfunction "RST_11") (pintype "bidirectional"))
    )
    (net (code "94") (name "unconnected-(U5-RTS-Pad4)") (class "Default")
      (node (ref "U5") (pin "4") (pinfunction "RTS_4") (pintype "bidirectional"))
    )
    (net (code "95") (name "unconnected-(U5-VBUSD+-Pad20)") (class "Default")
      (node (ref "U5") (pin "20") (pinfunction "VBUSD+_20") (pintype "bidirectional"))
    )
    (net (code "96") (name "unconnected-(U5-VBUSD--Pad15)") (class "Default")
      (node (ref "U5") (pin "15") (pinfunction "VBUSD-_15") (pintype "bidirectional"))
    )
    (net (code "97") (name "unconnected-(U8-DRDY-Pad15)") (class "Default")
      (node (ref "U8") (pin "15") (pinfunction "DRDY_15") (pintype "bidirectional"))
    )
    (net (code "98") (name "unconnected-(U8-NC-Pad3)") (class "Default")
      (node (ref "U8") (pin "3") (pinfunction "NC_3") (pintype "bidirectional"))
    )
    (net (code "99") (name "unconnected-(U8-NC-Pad5)") (class "Default")
      (node (ref "U8") (pin "5") (pinfunction "NC_5") (pintype "bidirectional"))
    )
    (net (code "100") (name "unconnected-(U8-NC-Pad6)") (class "Default")
      (node (ref "U8") (pin "6") (pinfunction "NC_6") (pintype "bidirectional"))
    )
    (net (code "101") (name "unconnected-(U8-NC-Pad7)") (class "Default")
      (node (ref "U8") (pin "7") (pinfunction "NC_7") (pintype "bidirectional"))
    )
    (net (code "102") (name "unconnected-(U8-NC-Pad14)") (class "Default")
      (node (ref "U8") (pin "14") (pinfunction "NC_14") (pintype "bidirectional"))
    )
    (net (code "103") (name "unconnected-(U9-BP-Pad4)") (class "Default")
      (node (ref "U9") (pin "4") (pinfunction "BP_4") (pintype "input"))
    )
  )
)
